# TrinketBlinkM0B.net
KiCad netlist of a schematic drawn in EAGLE
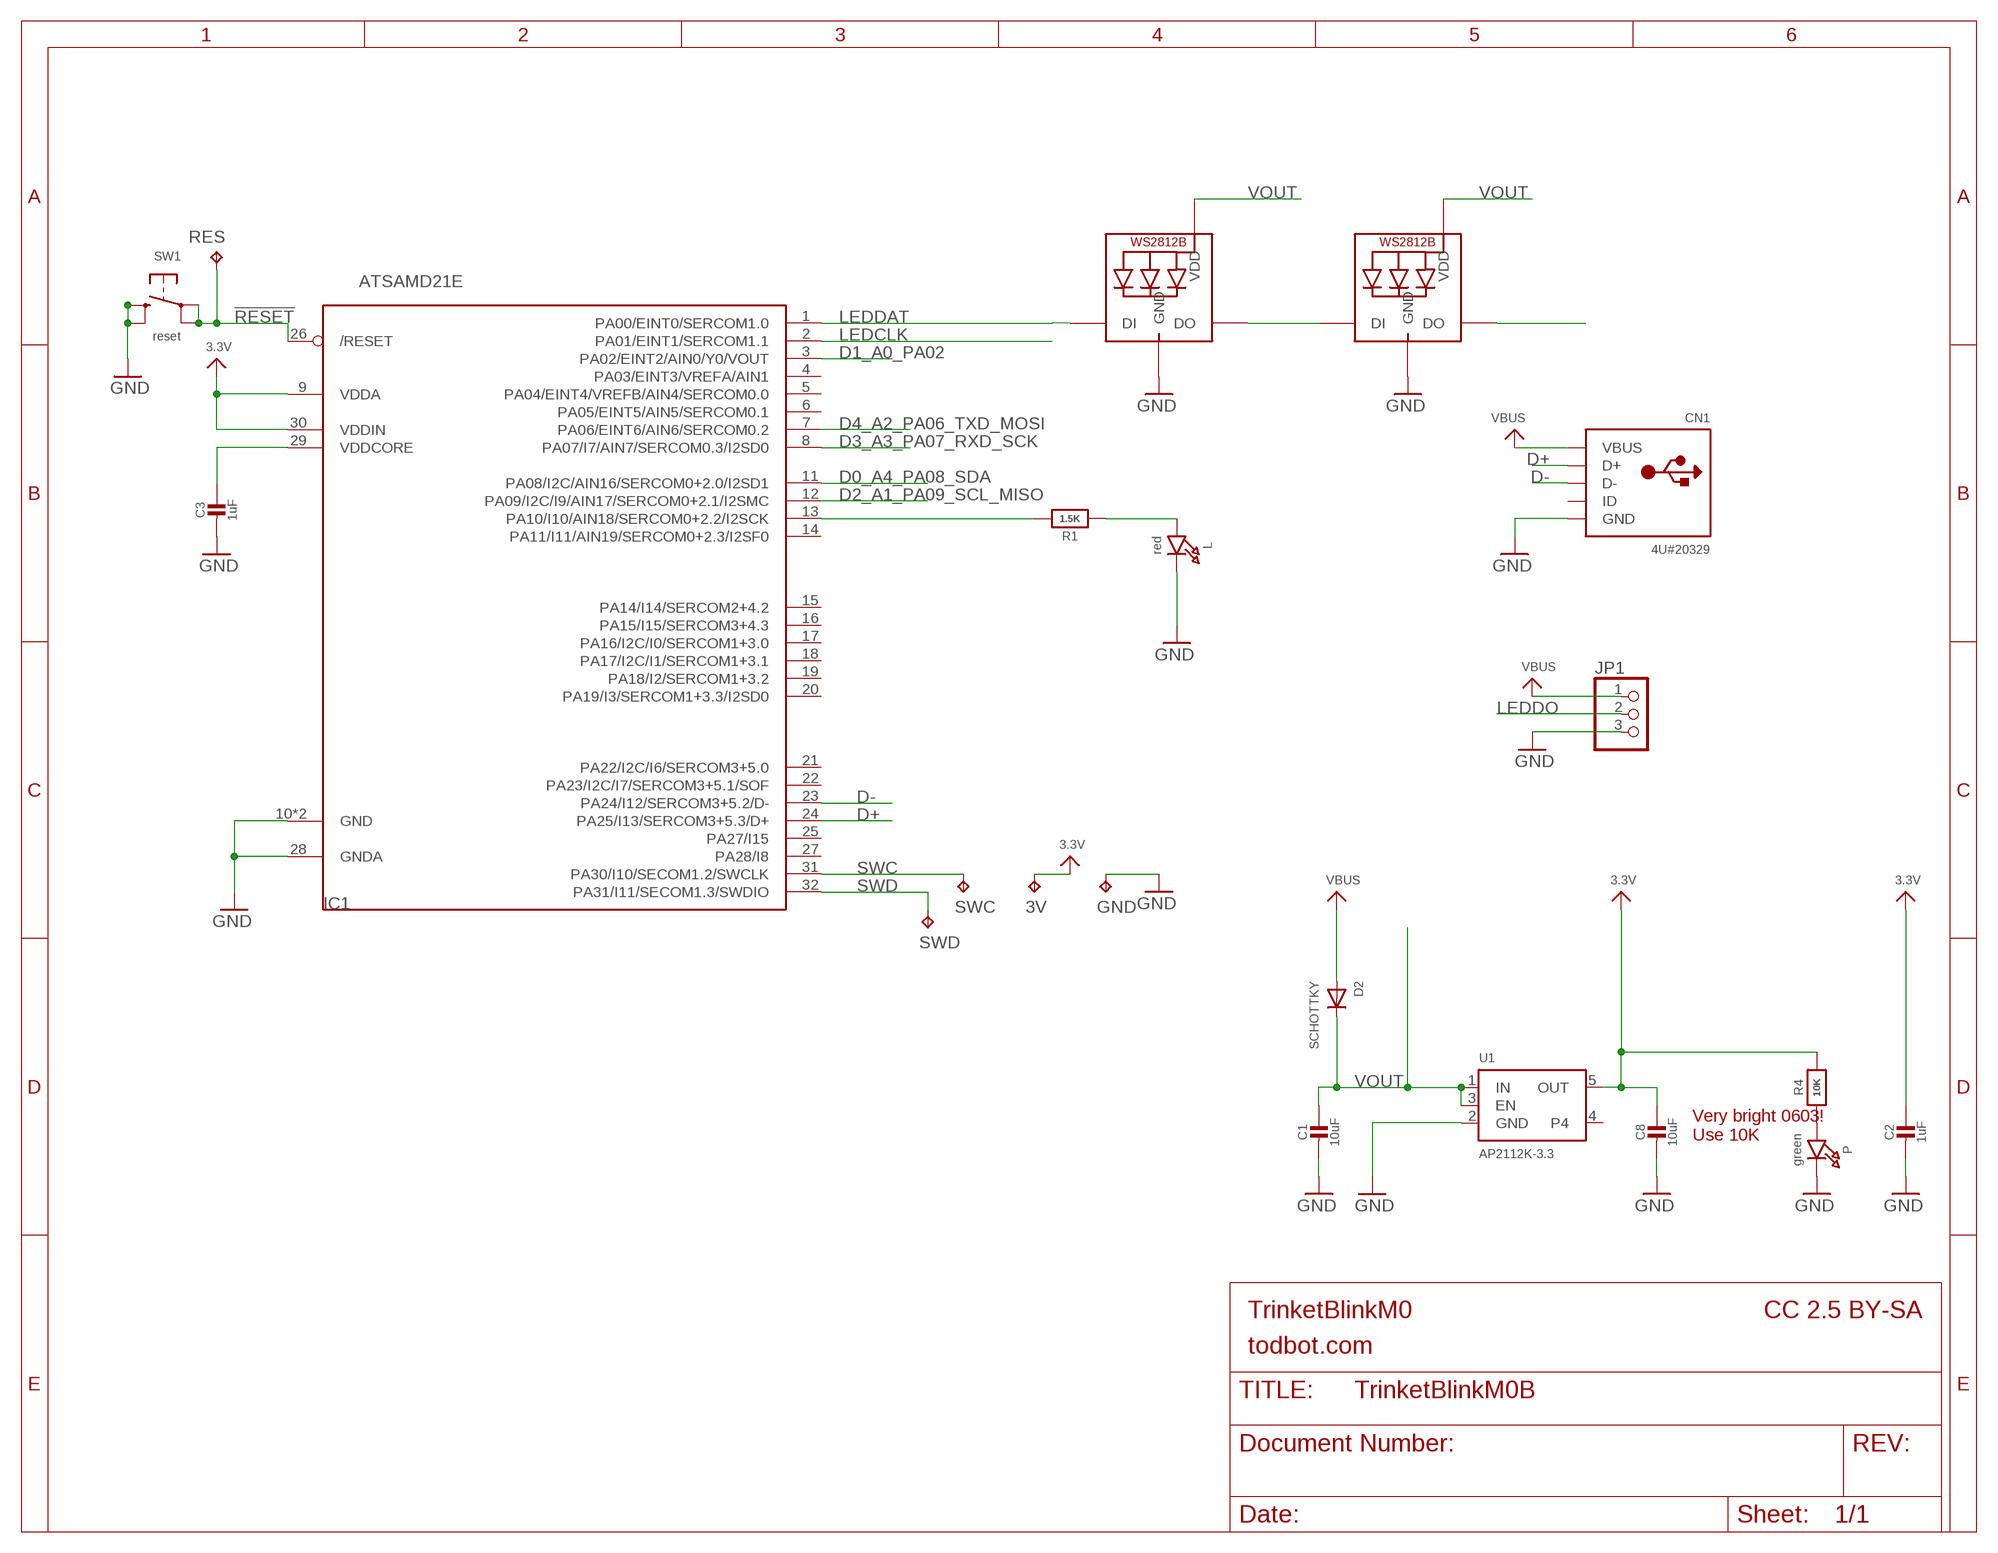
[diagram p0: schematic, sheet 1]

(export (version "E")
  (design (tool "Eeschema 10.0.6"))
  (components
    (comp (ref "3V")
      (value "TPB1,27")
      (footprint "eagle-import:B1,27")
      (libsource (lib "eagle-import") (part "TPB1,27"))
    )
    (comp (ref "C1")
      (value "10uF")
      (footprint "eagle-import:0805-NO")
      (libsource (lib "eagle-import") (part "CAP_CERAMIC0805-NOOUTLINE"))
    )
    (comp (ref "C2")
      (value "1uF")
      (footprint "eagle-import:0603-NO")
      (libsource (lib "eagle-import") (part "CAP_CERAMIC0603_NO"))
    )
    (comp (ref "C3")
      (value "1uF")
      (footprint "eagle-import:0603-NO")
      (libsource (lib "eagle-import") (part "CAP_CERAMIC0603_NO"))
    )
    (comp (ref "C8")
      (value "10uF")
      (footprint "eagle-import:0805-NO")
      (libsource (lib "eagle-import") (part "CAP_CERAMIC0805-NOOUTLINE"))
    )
    (comp (ref "CN1")
      (value "4U#20329")
      (footprint "eagle-import:4UCONN_20329_V2")
      (libsource (lib "eagle-import") (part "USB_MICRO_20329_V2"))
    )
    (comp (ref "D2")
      (value "SCHOTTKY")
      (footprint "eagle-import:SOD-123FL")
      (libsource (lib "eagle-import") (part "DIODE_SOD-123FL"))
    )
    (comp (ref "GND")
      (value "TPB1,27")
      (footprint "eagle-import:B1,27")
      (libsource (lib "eagle-import") (part "TPB1,27"))
    )
    (comp (ref "IC1")
      (value "ATSAMD21E")
      (footprint "eagle-import:QFN32_5MM")
      (libsource (lib "eagle-import") (part "ATSAMD21E"))
    )
    (comp (ref "JP1")
      (value "PINHD-1X3CB")
      (footprint "eagle-import:1X03-CLEANBIG")
      (libsource (lib "eagle-import") (part "PINHD-1X3CB"))
    )
    (comp (ref "L")
      (value "red")
      (footprint "eagle-import:CHIPLED_0603_NOOUTLINE")
      (libsource (lib "eagle-import") (part "LED0603_NOOUTLINE"))
    )
    (comp (ref "LED1")
      (value "WS2812B_5050N")
      (footprint "eagle-import:WS2812B-NARROW")
      (libsource (lib "eagle-import") (part "WS2812B_5050N"))
    )
    (comp (ref "LED2")
      (value "WS2812B_5050N")
      (footprint "eagle-import:WS2812B-NARROW")
      (libsource (lib "eagle-import") (part "WS2812B_5050N"))
    )
    (comp (ref "P")
      (value "green")
      (footprint "eagle-import:CHIPLED_0603_NOOUTLINE")
      (libsource (lib "eagle-import") (part "LED0603_NOOUTLINE"))
    )
    (comp (ref "R1")
      (value "1.5K")
      (footprint "eagle-import:0603-NO")
      (libsource (lib "eagle-import") (part "RESISTOR_0603_NOOUT"))
    )
    (comp (ref "R4")
      (value "10K")
      (footprint "eagle-import:0603-NO")
      (libsource (lib "eagle-import") (part "RESISTOR_0603_NOOUT"))
    )
    (comp (ref "RES")
      (value "TPB1,27")
      (footprint "eagle-import:B1,27")
      (libsource (lib "eagle-import") (part "TPB1,27"))
    )
    (comp (ref "SW1")
      (value "reset")
      (footprint "eagle-import:BTN_KMR2_4.6X2.8")
      (libsource (lib "eagle-import") (part "SWITCH_TACT_SMT4.6X2.8"))
    )
    (comp (ref "SWC")
      (value "TPB1,27")
      (footprint "eagle-import:B1,27")
      (libsource (lib "eagle-import") (part "TPB1,27"))
    )
    (comp (ref "SWD")
      (value "TPB1,27")
      (footprint "eagle-import:B1,27")
      (libsource (lib "eagle-import") (part "TPB1,27"))
    )
    (comp (ref "U1")
      (value "AP2112K-3.3")
      (footprint "eagle-import:SOT23-5")
      (libsource (lib "eagle-import") (part "VREG_SOT23-5"))
    )
  )
  (nets
    (net (code "1") (name "/D+") (class "Default")
      (node (ref "CN1") (pin "D+") (pinfunction "D+_D+") (pintype "bidirectional"))
      (node (ref "IC1") (pin "24") (pinfunction "PA25/I13/SERCOM3+5.3/D+_24") (pintype "bidirectional"))
    )
    (net (code "2") (name "/D-") (class "Default")
      (node (ref "CN1") (pin "D-") (pinfunction "D-_D-") (pintype "bidirectional"))
      (node (ref "IC1") (pin "23") (pinfunction "PA24/I12/SERCOM3+5.2/D-_23") (pintype "bidirectional"))
    )
    (net (code "3") (name "/D0_A4_PA08_SDA") (class "Default")
      (node (ref "IC1") (pin "11") (pinfunction "PA08/I2C/AIN16/SERCOM0+2.0/I2SD1_11") (pintype "bidirectional"))
    )
    (net (code "4") (name "/D1_A0_PA02") (class "Default")
      (node (ref "IC1") (pin "3") (pinfunction "PA02/EINT2/AIN0/Y0/VOUT_3") (pintype "bidirectional"))
    )
    (net (code "5") (name "/D2_A1_PA09_SCL_MISO") (class "Default")
      (node (ref "IC1") (pin "12") (pinfunction "PA09/I2C/I9/AIN17/SERCOM0+2.1/I2SMC_12") (pintype "bidirectional"))
    )
    (net (code "6") (name "/D3_A3_PA07_RXD_SCK") (class "Default")
      (node (ref "IC1") (pin "8") (pinfunction "PA07/I7/AIN7/SERCOM0.3/I2SD0_8") (pintype "bidirectional"))
    )
    (net (code "7") (name "/D4_A2_PA06_TXD_MOSI") (class "Default")
      (node (ref "IC1") (pin "7") (pinfunction "PA06/EINT6/AIN6/SERCOM0.2_7") (pintype "bidirectional"))
    )
    (net (code "8") (name "/LEDCLK") (class "Default")
      (node (ref "IC1") (pin "2") (pinfunction "PA01/EINT1/SERCOM1.1_2") (pintype "bidirectional"))
    )
    (net (code "9") (name "/LEDDAT") (class "Default")
      (node (ref "IC1") (pin "1") (pinfunction "PA00/EINT0/SERCOM1.0_1") (pintype "bidirectional"))
      (node (ref "LED1") (pin "4-DIN") (pinfunction "DI_4-DIN") (pintype "input"))
    )
    (net (code "10") (name "/LEDDO") (class "Default")
      (node (ref "JP1") (pin "2") (pinfunction "2_2") (pintype "passive"))
      (node (ref "LED2") (pin "2-DOUT") (pinfunction "DO_2-DOUT") (pintype "output"))
    )
    (net (code "11") (name "/SWC") (class "Default")
      (node (ref "IC1") (pin "31") (pinfunction "PA30/I10/SECOM1.2/SWCLK_31") (pintype "bidirectional"))
      (node (ref "SWC") (pin "TP") (pinfunction "TP_TP") (pintype "input"))
    )
    (net (code "12") (name "/SWD") (class "Default")
      (node (ref "IC1") (pin "32") (pinfunction "PA31/I11/SECOM1.3/SWDIO_32") (pintype "bidirectional"))
      (node (ref "SWD") (pin "TP") (pinfunction "TP_TP") (pintype "input"))
    )
    (net (code "13") (name "/VOUT") (class "Default")
      (node (ref "C1") (pin "1") (pinfunction "1_1") (pintype "passive"))
      (node (ref "D2") (pin "C") (pinfunction "C_C") (pintype "passive"))
      (node (ref "LED1") (pin "1-VDD") (pinfunction "VDD_1-VDD") (pintype "power_in"))
      (node (ref "LED2") (pin "1-VDD") (pinfunction "VDD_1-VDD") (pintype "power_in"))
      (node (ref "U1") (pin "1") (pinfunction "IN_1") (pintype "power_in"))
      (node (ref "U1") (pin "3") (pinfunction "EN_3") (pintype "input"))
    )
    (net (code "14") (name "/~{RESET}") (class "Default")
      (node (ref "IC1") (pin "26") (pinfunction "/RESET_26") (pintype "bidirectional"))
      (node (ref "RES") (pin "TP") (pinfunction "TP_TP") (pintype "input"))
      (node (ref "SW1") (pin "A") (pinfunction "P_A") (pintype "passive"))
      (node (ref "SW1") (pin "A'") (pinfunction "P1_A'") (pintype "passive"))
    )
    (net (code "15") (name "3.3V") (class "Default")
      (node (ref "3V") (pin "TP") (pinfunction "TP_TP") (pintype "input"))
      (node (ref "C2") (pin "1") (pinfunction "1_1") (pintype "passive"))
      (node (ref "C8") (pin "1") (pinfunction "1_1") (pintype "passive"))
      (node (ref "IC1") (pin "30") (pinfunction "VDDIN_30") (pintype "power_in"))
      (node (ref "IC1") (pin "9") (pinfunction "VDDA_9") (pintype "power_in"))
      (node (ref "R4") (pin "2") (pinfunction "2_2") (pintype "passive"))
      (node (ref "U1") (pin "5") (pinfunction "OUT_5") (pintype "power_in"))
    )
    (net (code "16") (name "GND") (class "Default")
      (node (ref "C1") (pin "2") (pinfunction "2_2") (pintype "passive"))
      (node (ref "C2") (pin "2") (pinfunction "2_2") (pintype "passive"))
      (node (ref "C3") (pin "2") (pinfunction "2_2") (pintype "passive"))
      (node (ref "C8") (pin "2") (pinfunction "2_2") (pintype "passive"))
      (node (ref "CN1") (pin "BASE@1") (pinfunction "GND_BASE@1") (pintype "power_in"))
      (node (ref "CN1") (pin "BASE@2") (pinfunction "GND_BASE@2") (pintype "power_in"))
      (node (ref "CN1") (pin "GND") (pinfunction "GND_GND") (pintype "power_in"))
      (node (ref "CN1") (pin "SPRT@1") (pinfunction "GND_SPRT@1") (pintype "power_in"))
      (node (ref "CN1") (pin "SPRT@2") (pinfunction "GND_SPRT@2") (pintype "power_in"))
      (node (ref "CN1") (pin "SPRT@3") (pinfunction "GND_SPRT@3") (pintype "power_in"))
      (node (ref "CN1") (pin "SPRT@4") (pinfunction "GND_SPRT@4") (pintype "power_in"))
      (node (ref "GND") (pin "TP") (pinfunction "TP_TP") (pintype "input"))
      (node (ref "IC1") (pin "10") (pinfunction "GND_10") (pintype "power_in"))
      (node (ref "IC1") (pin "28") (pinfunction "GNDA_28") (pintype "power_in"))
      (node (ref "IC1") (pin "33") (pinfunction "GND_33") (pintype "power_in"))
      (node (ref "JP1") (pin "3") (pinfunction "3_3") (pintype "passive"))
      (node (ref "L") (pin "C") (pinfunction "C_C") (pintype "passive"))
      (node (ref "LED1") (pin "3-GND") (pinfunction "GND_3-GND") (pintype "power_in"))
      (node (ref "LED2") (pin "3-GND") (pinfunction "GND_3-GND") (pintype "power_in"))
      (node (ref "P") (pin "C") (pinfunction "C_C") (pintype "passive"))
      (node (ref "SW1") (pin "B") (pinfunction "S_B") (pintype "passive"))
      (node (ref "SW1") (pin "B'") (pinfunction "S1_B'") (pintype "passive"))
      (node (ref "U1") (pin "2") (pinfunction "GND_2") (pintype "power_in"))
    )
    (net (code "17") (name "Net-(IC1-PA10{slash}I10{slash}AIN18{slash}SERCOM0+2.2{slash}I2SCK)") (class "Default")
      (node (ref "IC1") (pin "13") (pinfunction "PA10/I10/AIN18/SERCOM0+2.2/I2SCK_13") (pintype "bidirectional"))
      (node (ref "R1") (pin "2") (pinfunction "2_2") (pintype "passive"))
    )
    (net (code "18") (name "Net-(IC1-VDDCORE)") (class "Default")
      (node (ref "C3") (pin "1") (pinfunction "1_1") (pintype "passive"))
      (node (ref "IC1") (pin "29") (pinfunction "VDDCORE_29") (pintype "power_in"))
    )
    (net (code "19") (name "Net-(L-PadA)") (class "Default")
      (node (ref "L") (pin "A") (pinfunction "A_A") (pintype "passive"))
      (node (ref "R1") (pin "1") (pinfunction "1_1") (pintype "passive"))
    )
    (net (code "20") (name "Net-(LED1-DO)") (class "Default")
      (node (ref "LED1") (pin "2-DOUT") (pinfunction "DO_2-DOUT") (pintype "output"))
      (node (ref "LED2") (pin "4-DIN") (pinfunction "DI_4-DIN") (pintype "input"))
    )
    (net (code "21") (name "Net-(P-PadA)") (class "Default")
      (node (ref "P") (pin "A") (pinfunction "A_A") (pintype "passive"))
      (node (ref "R4") (pin "1") (pinfunction "1_1") (pintype "passive"))
    )
    (net (code "22") (name "VBUS") (class "Default")
      (node (ref "CN1") (pin "VBUS") (pinfunction "VBUS_VBUS") (pintype "power_in"))
      (node (ref "D2") (pin "A") (pinfunction "A_A") (pintype "passive"))
      (node (ref "JP1") (pin "1") (pinfunction "1_1") (pintype "passive"))
    )
    (net (code "23") (name "unconnected-(CN1-PadID)") (class "Default")
      (node (ref "CN1") (pin "ID") (pinfunction "ID_ID") (pintype "bidirectional"))
    )
    (net (code "24") (name "unconnected-(IC1-PA03{slash}EINT3{slash}VREFA{slash}AIN1-Pad4)") (class "Default")
      (node (ref "IC1") (pin "4") (pinfunction "PA03/EINT3/VREFA/AIN1_4") (pintype "bidirectional"))
    )
    (net (code "25") (name "unconnected-(IC1-PA04{slash}EINT4{slash}VREFB{slash}AIN4{slash}SERCOM0.0-Pad5)") (class "Default")
      (node (ref "IC1") (pin "5") (pinfunction "PA04/EINT4/VREFB/AIN4/SERCOM0.0_5") (pintype "bidirectional"))
    )
    (net (code "26") (name "unconnected-(IC1-PA05{slash}EINT5{slash}AIN5{slash}SERCOM0.1-Pad6)") (class "Default")
      (node (ref "IC1") (pin "6") (pinfunction "PA05/EINT5/AIN5/SERCOM0.1_6") (pintype "bidirectional"))
    )
    (net (code "27") (name "unconnected-(IC1-PA11{slash}I11{slash}AIN19{slash}SERCOM0+2.3{slash}I2SF0-Pad14)") (class "Default")
      (node (ref "IC1") (pin "14") (pinfunction "PA11/I11/AIN19/SERCOM0+2.3/I2SF0_14") (pintype "bidirectional"))
    )
    (net (code "28") (name "unconnected-(IC1-PA14{slash}I14{slash}SERCOM2+4.2-Pad15)") (class "Default")
      (node (ref "IC1") (pin "15") (pinfunction "PA14/I14/SERCOM2+4.2_15") (pintype "bidirectional"))
    )
    (net (code "29") (name "unconnected-(IC1-PA15{slash}I15{slash}SERCOM3+4.3-Pad16)") (class "Default")
      (node (ref "IC1") (pin "16") (pinfunction "PA15/I15/SERCOM3+4.3_16") (pintype "bidirectional"))
    )
    (net (code "30") (name "unconnected-(IC1-PA16{slash}I2C{slash}I0{slash}SERCOM1+3.0-Pad17)") (class "Default")
      (node (ref "IC1") (pin "17") (pinfunction "PA16/I2C/I0/SERCOM1+3.0_17") (pintype "bidirectional"))
    )
    (net (code "31") (name "unconnected-(IC1-PA17{slash}I2C{slash}I1{slash}SERCOM1+3.1-Pad18)") (class "Default")
      (node (ref "IC1") (pin "18") (pinfunction "PA17/I2C/I1/SERCOM1+3.1_18") (pintype "bidirectional"))
    )
    (net (code "32") (name "unconnected-(IC1-PA18{slash}I2{slash}SERCOM1+3.2-Pad19)") (class "Default")
      (node (ref "IC1") (pin "19") (pinfunction "PA18/I2/SERCOM1+3.2_19") (pintype "bidirectional"))
    )
    (net (code "33") (name "unconnected-(IC1-PA19{slash}I3{slash}SERCOM1+3.3{slash}I2SD0-Pad20)") (class "Default")
      (node (ref "IC1") (pin "20") (pinfunction "PA19/I3/SERCOM1+3.3/I2SD0_20") (pintype "bidirectional"))
    )
    (net (code "34") (name "unconnected-(IC1-PA22{slash}I2C{slash}I6{slash}SERCOM3+5.0-Pad21)") (class "Default")
      (node (ref "IC1") (pin "21") (pinfunction "PA22/I2C/I6/SERCOM3+5.0_21") (pintype "bidirectional"))
    )
    (net (code "35") (name "unconnected-(IC1-PA23{slash}I2C{slash}I7{slash}SERCOM3+5.1{slash}SOF-Pad22)") (class "Default")
      (node (ref "IC1") (pin "22") (pinfunction "PA23/I2C/I7/SERCOM3+5.1/SOF_22") (pintype "bidirectional"))
    )
    (net (code "36") (name "unconnected-(IC1-PA27{slash}I15-Pad25)") (class "Default")
      (node (ref "IC1") (pin "25") (pinfunction "PA27/I15_25") (pintype "bidirectional"))
    )
    (net (code "37") (name "unconnected-(IC1-PA28{slash}I8-Pad27)") (class "Default")
      (node (ref "IC1") (pin "27") (pinfunction "PA28/I8_27") (pintype "bidirectional"))
    )
    (net (code "38") (name "unconnected-(U1-P4-Pad4)") (class "Default")
      (node (ref "U1") (pin "4") (pinfunction "P4_4") (pintype "bidirectional"))
    )
  )
)
